# as5050-dev-board.net
KiCad netlist of a schematic drawn in EAGLE
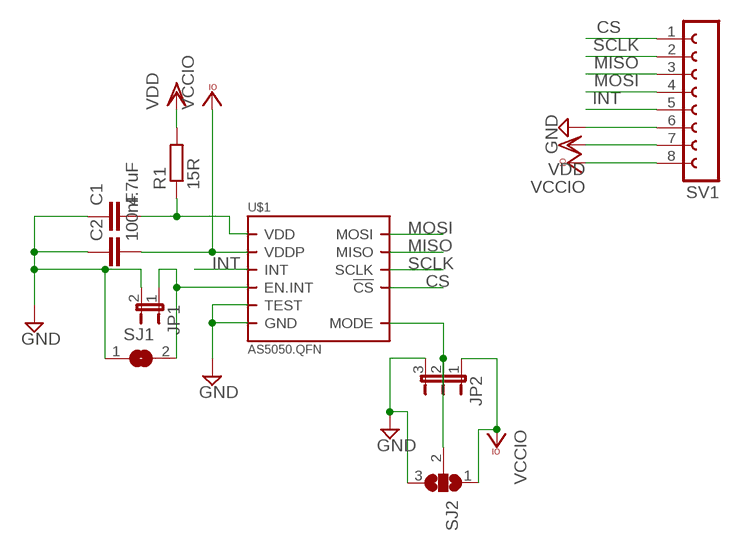
[diagram p0: schematic, sheet 1]

(export (version "E")
  (design (tool "Eeschema 10.0.6"))
  (components
    (comp (ref "C1")
      (value "4.7uF")
      (footprint "eagle-import:C0805")
      (libsource (lib "eagle-import") (part "C-EUC0805"))
    )
    (comp (ref "C2")
      (value "100nF")
      (footprint "eagle-import:C0805")
      (libsource (lib "eagle-import") (part "C-EUC0805"))
    )
    (comp (ref "JP1")
      (value "JP1E")
      (footprint "eagle-import:JP1")
      (libsource (lib "eagle-import") (part "JP1E"))
    )
    (comp (ref "JP2")
      (value "JP2E")
      (footprint "eagle-import:JP2")
      (libsource (lib "eagle-import") (part "JP2E"))
    )
    (comp (ref "R1")
      (value "15R")
      (footprint "eagle-import:R0805")
      (libsource (lib "eagle-import") (part "R-EU_R0805"))
    )
    (comp (ref "SJ1") (value "SJ") (footprint "eagle-import:SJ") (libsource (lib "eagle-import") (part "SJ")))
    (comp (ref "SJ2")
      (value "SJ2W")
      (footprint "eagle-import:SJ_2")
      (libsource (lib "eagle-import") (part "SJ2W"))
    )
    (comp (ref "SV1")
      (value "FE08-1")
      (footprint "eagle-import:FE08")
      (libsource (lib "eagle-import") (part "FE08-1"))
    )
    (comp (ref "U$1")
      (value "AS5050.QFN")
      (footprint "eagle-import:QFN.16")
      (fields (field (name "MF") "ams") (field (name "MP") "AS5050"))
      (libsource (lib "eagle-import") (part "AS5050.QFN"))
    )
  )
  (nets
    (net (code "1") (name "/CS") (class "Default")
      (node (ref "SV1") (pin "1") (pinfunction "1_1") (pintype "passive"))
      (node (ref "U$1") (pin "4") (pinfunction "~{CS}_4") (pintype "bidirectional"))
    )
    (net (code "2") (name "/INT") (class "Default")
      (node (ref "SV1") (pin "5") (pinfunction "5_5") (pintype "passive"))
      (node (ref "U$1") (pin "15") (pinfunction "INT_15") (pintype "bidirectional"))
    )
    (net (code "3") (name "/MISO") (class "Default")
      (node (ref "SV1") (pin "3") (pinfunction "3_3") (pintype "passive"))
      (node (ref "U$1") (pin "2") (pinfunction "MISO_2") (pintype "bidirectional"))
    )
    (net (code "4") (name "/MOSI") (class "Default")
      (node (ref "SV1") (pin "4") (pinfunction "4_4") (pintype "passive"))
      (node (ref "U$1") (pin "1") (pinfunction "MOSI_1") (pintype "bidirectional"))
    )
    (net (code "5") (name "/SCLK") (class "Default")
      (node (ref "SV1") (pin "2") (pinfunction "2_2") (pintype "passive"))
      (node (ref "U$1") (pin "3") (pinfunction "SCLK_3") (pintype "bidirectional"))
    )
    (net (code "6") (name "GND") (class "Default")
      (node (ref "C1") (pin "1") (pinfunction "1_1") (pintype "passive"))
      (node (ref "C2") (pin "1") (pinfunction "1_1") (pintype "passive"))
      (node (ref "JP1") (pin "2") (pinfunction "2_2") (pintype "passive"))
      (node (ref "JP2") (pin "3") (pinfunction "3_3") (pintype "passive"))
      (node (ref "SJ1") (pin "1") (pinfunction "1_1") (pintype "passive"))
      (node (ref "SJ2") (pin "3") (pinfunction "3_3") (pintype "passive"))
      (node (ref "SV1") (pin "6") (pinfunction "6_6") (pintype "passive"))
      (node (ref "U$1") (pin "13") (pinfunction "GND_13") (pintype "bidirectional"))
      (node (ref "U$1") (pin "9") (pinfunction "TEST_9") (pintype "bidirectional"))
    )
    (net (code "7") (name "Net-(U$1-EN.INT)") (class "Default")
      (node (ref "JP1") (pin "1") (pinfunction "1_1") (pintype "passive"))
      (node (ref "SJ1") (pin "2") (pinfunction "2_2") (pintype "passive"))
      (node (ref "U$1") (pin "10") (pinfunction "EN.INT_10") (pintype "bidirectional"))
    )
    (net (code "8") (name "Net-(U$1-MODE)") (class "Default")
      (node (ref "JP2") (pin "2") (pinfunction "2_2") (pintype "passive"))
      (node (ref "SJ2") (pin "2") (pinfunction "2_2") (pintype "passive"))
      (node (ref "U$1") (pin "14") (pinfunction "MODE_14") (pintype "bidirectional"))
    )
    (net (code "9") (name "Net-(U$1-VDD)") (class "Default")
      (node (ref "C1") (pin "2") (pinfunction "2_2") (pintype "passive"))
      (node (ref "R1") (pin "1") (pinfunction "1_1") (pintype "passive"))
      (node (ref "U$1") (pin "12") (pinfunction "VDD_12") (pintype "bidirectional"))
    )
    (net (code "10") (name "VCCIO") (class "Default")
      (node (ref "C2") (pin "2") (pinfunction "2_2") (pintype "passive"))
      (node (ref "JP2") (pin "1") (pinfunction "1_1") (pintype "passive"))
      (node (ref "SJ2") (pin "1") (pinfunction "1_1") (pintype "passive"))
      (node (ref "SV1") (pin "8") (pinfunction "8_8") (pintype "passive"))
      (node (ref "U$1") (pin "11") (pinfunction "VDDP_11") (pintype "bidirectional"))
    )
    (net (code "11") (name "VDD") (class "Default")
      (node (ref "R1") (pin "2") (pinfunction "2_2") (pintype "passive"))
      (node (ref "SV1") (pin "7") (pinfunction "7_7") (pintype "passive"))
    )
  )
)
